# oven.net
KiCad netlist of a schematic drawn in EAGLE
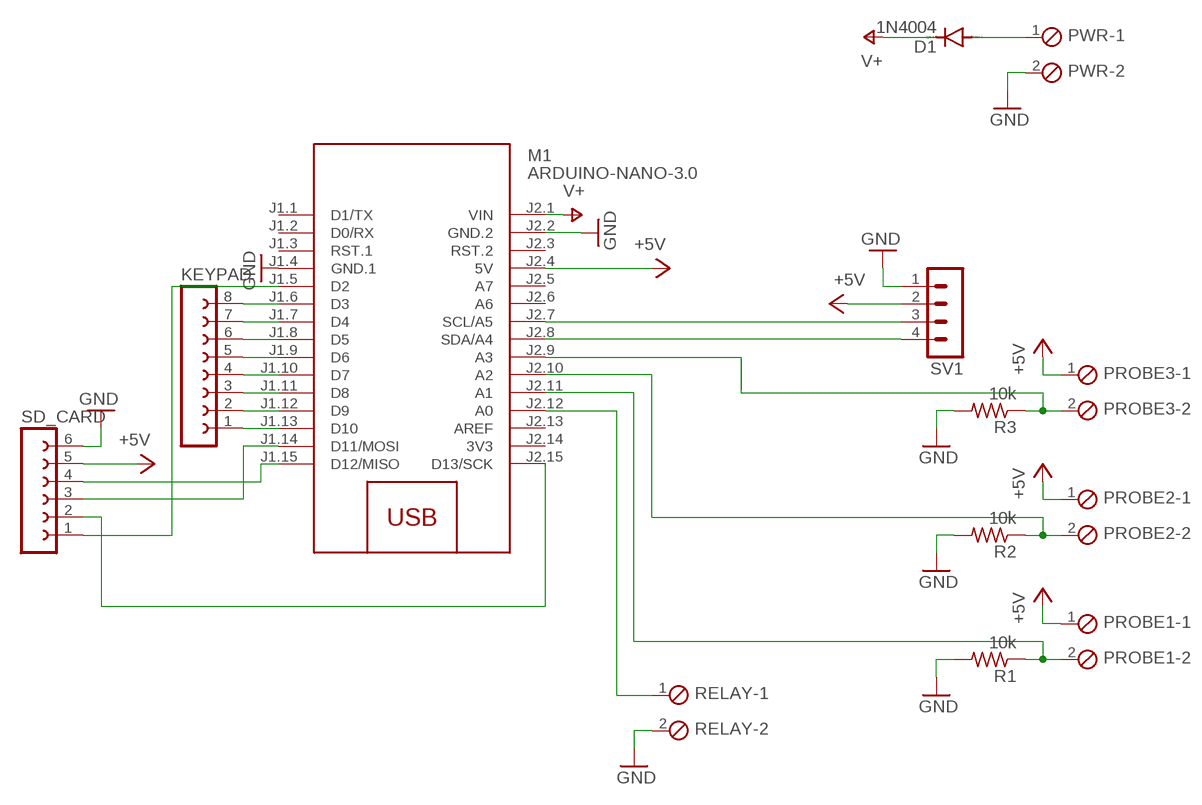
[diagram p0: schematic, sheet 1]

(export (version "E")
  (design (tool "Eeschema 10.0.6"))
  (components
    (comp (ref "D1")
      (value "1N4004")
      (footprint "eagle-import:DO41-10")
      (libsource (lib "eagle-import") (part "1N4004"))
    )
    (comp (ref "KEYPAD")
      (value "FE08-1")
      (footprint "eagle-import:FE08")
      (libsource (lib "eagle-import") (part "FE08-1"))
    )
    (comp (ref "M1")
      (value "ARDUINO-NANO-3.0")
      (footprint "eagle-import:ARDUINO-NANO-3.0")
      (libsource (lib "eagle-import") (part "ARDUINO-NANO-3.0"))
    )
    (comp (ref "PROBE1")
      (value "MPT2")
      (footprint "eagle-import:2POL254")
      (libsource (lib "eagle-import") (part "MPT2"))
    )
    (comp (ref "PROBE2")
      (value "MPT2")
      (footprint "eagle-import:2POL254")
      (libsource (lib "eagle-import") (part "MPT2"))
    )
    (comp (ref "PROBE3")
      (value "MPT2")
      (footprint "eagle-import:2POL254")
      (libsource (lib "eagle-import") (part "MPT2"))
    )
    (comp (ref "PWR")
      (value "MPT2")
      (footprint "eagle-import:2POL254")
      (libsource (lib "eagle-import") (part "MPT2"))
    )
    (comp (ref "R1")
      (value "10k")
      (footprint "eagle-import:0204_5")
      (libsource (lib "eagle-import") (part "R-US_0204/5"))
    )
    (comp (ref "R2")
      (value "10k")
      (footprint "eagle-import:0204_5")
      (libsource (lib "eagle-import") (part "R-US_0204/5"))
    )
    (comp (ref "R3")
      (value "10k")
      (footprint "eagle-import:0204_5")
      (libsource (lib "eagle-import") (part "R-US_0204/5"))
    )
    (comp (ref "RELAY")
      (value "MPT2")
      (footprint "eagle-import:2POL254")
      (libsource (lib "eagle-import") (part "MPT2"))
    )
    (comp (ref "SD_CARD")
      (value "FE06W")
      (footprint "eagle-import:FE06W")
      (libsource (lib "eagle-import") (part "FE06W"))
    )
    (comp (ref "SV1")
      (value "MA04-1")
      (footprint "eagle-import:MA04-1")
      (libsource (lib "eagle-import") (part "MA04-1"))
    )
  )
  (nets
    (net (code "1") (name "+5V") (class "Default")
      (node (ref "M1") (pin "J2.4") (pinfunction "5V_J2.4") (pintype "power_in"))
      (node (ref "PROBE1") (pin "1") (pinfunction "1_1") (pintype "passive"))
      (node (ref "PROBE2") (pin "1") (pinfunction "1_1") (pintype "passive"))
      (node (ref "PROBE3") (pin "1") (pinfunction "1_1") (pintype "passive"))
      (node (ref "SD_CARD") (pin "5") (pinfunction "5_5") (pintype "passive"))
      (node (ref "SV1") (pin "2") (pinfunction "2_2") (pintype "passive"))
    )
    (net (code "2") (name "/3V3") (class "Default")
      (node (ref "M1") (pin "J2.14") (pinfunction "3V3_J2.14") (pintype "power_in"))
    )
    (net (code "3") (name "GND") (class "Default")
      (node (ref "M1") (pin "J1.4") (pinfunction "GND.1_J1.4") (pintype "power_in"))
      (node (ref "M1") (pin "J2.2") (pinfunction "GND.2_J2.2") (pintype "power_in"))
      (node (ref "PWR") (pin "2") (pinfunction "1_2") (pintype "passive"))
      (node (ref "R1") (pin "2") (pinfunction "2_2") (pintype "passive"))
      (node (ref "R2") (pin "2") (pinfunction "2_2") (pintype "passive"))
      (node (ref "R3") (pin "2") (pinfunction "2_2") (pintype "passive"))
      (node (ref "RELAY") (pin "2") (pinfunction "1_2") (pintype "passive"))
      (node (ref "SD_CARD") (pin "6") (pinfunction "6_6") (pintype "passive"))
      (node (ref "SV1") (pin "1") (pinfunction "1_1") (pintype "passive"))
    )
    (net (code "4") (name "Net-(D1-PadA)") (class "Default")
      (node (ref "D1") (pin "A") (pinfunction "A_A") (pintype "passive"))
      (node (ref "PWR") (pin "1") (pinfunction "1_1") (pintype "passive"))
    )
    (net (code "5") (name "Net-(M1-A0)") (class "Default")
      (node (ref "M1") (pin "J2.12") (pinfunction "A0_J2.12") (pintype "bidirectional"))
      (node (ref "RELAY") (pin "1") (pinfunction "1_1") (pintype "passive"))
    )
    (net (code "6") (name "Net-(M1-A1)") (class "Default")
      (node (ref "M1") (pin "J2.11") (pinfunction "A1_J2.11") (pintype "bidirectional"))
      (node (ref "PROBE1") (pin "2") (pinfunction "1_2") (pintype "passive"))
      (node (ref "R1") (pin "1") (pinfunction "1_1") (pintype "passive"))
    )
    (net (code "7") (name "Net-(M1-A2)") (class "Default")
      (node (ref "M1") (pin "J2.10") (pinfunction "A2_J2.10") (pintype "bidirectional"))
      (node (ref "PROBE2") (pin "2") (pinfunction "1_2") (pintype "passive"))
      (node (ref "R2") (pin "1") (pinfunction "1_1") (pintype "passive"))
    )
    (net (code "8") (name "Net-(M1-A3)") (class "Default")
      (node (ref "M1") (pin "J2.9") (pinfunction "A3_J2.9") (pintype "bidirectional"))
      (node (ref "PROBE3") (pin "2") (pinfunction "1_2") (pintype "passive"))
      (node (ref "R3") (pin "1") (pinfunction "1_1") (pintype "passive"))
    )
    (net (code "9") (name "Net-(M1-D2)") (class "Default")
      (node (ref "M1") (pin "J1.5") (pinfunction "D2_J1.5") (pintype "bidirectional"))
      (node (ref "SD_CARD") (pin "1") (pinfunction "1_1") (pintype "passive"))
    )
    (net (code "10") (name "Net-(M1-D3)") (class "Default")
      (node (ref "KEYPAD") (pin "8") (pinfunction "8_8") (pintype "passive"))
      (node (ref "M1") (pin "J1.6") (pinfunction "D3_J1.6") (pintype "bidirectional"))
    )
    (net (code "11") (name "Net-(M1-D4)") (class "Default")
      (node (ref "KEYPAD") (pin "7") (pinfunction "7_7") (pintype "passive"))
      (node (ref "M1") (pin "J1.7") (pinfunction "D4_J1.7") (pintype "bidirectional"))
    )
    (net (code "12") (name "Net-(M1-D5)") (class "Default")
      (node (ref "KEYPAD") (pin "6") (pinfunction "6_6") (pintype "passive"))
      (node (ref "M1") (pin "J1.8") (pinfunction "D5_J1.8") (pintype "bidirectional"))
    )
    (net (code "13") (name "Net-(M1-D6)") (class "Default")
      (node (ref "KEYPAD") (pin "5") (pinfunction "5_5") (pintype "passive"))
      (node (ref "M1") (pin "J1.9") (pinfunction "D6_J1.9") (pintype "bidirectional"))
    )
    (net (code "14") (name "Net-(M1-D7)") (class "Default")
      (node (ref "KEYPAD") (pin "4") (pinfunction "4_4") (pintype "passive"))
      (node (ref "M1") (pin "J1.10") (pinfunction "D7_J1.10") (pintype "bidirectional"))
    )
    (net (code "15") (name "Net-(M1-D8)") (class "Default")
      (node (ref "KEYPAD") (pin "3") (pinfunction "3_3") (pintype "passive"))
      (node (ref "M1") (pin "J1.11") (pinfunction "D8_J1.11") (pintype "bidirectional"))
    )
    (net (code "16") (name "Net-(M1-D9)") (class "Default")
      (node (ref "KEYPAD") (pin "2") (pinfunction "2_2") (pintype "passive"))
      (node (ref "M1") (pin "J1.12") (pinfunction "D9_J1.12") (pintype "bidirectional"))
    )
    (net (code "17") (name "Net-(M1-D10)") (class "Default")
      (node (ref "KEYPAD") (pin "1") (pinfunction "1_1") (pintype "passive"))
      (node (ref "M1") (pin "J1.13") (pinfunction "D10_J1.13") (pintype "bidirectional"))
    )
    (net (code "18") (name "Net-(M1-D11{slash}MOSI)") (class "Default")
      (node (ref "M1") (pin "J1.14") (pinfunction "D11/MOSI_J1.14") (pintype "bidirectional"))
      (node (ref "SD_CARD") (pin "3") (pinfunction "3_3") (pintype "passive"))
    )
    (net (code "19") (name "Net-(M1-D12{slash}MISO)") (class "Default")
      (node (ref "M1") (pin "J1.15") (pinfunction "D12/MISO_J1.15") (pintype "bidirectional"))
      (node (ref "SD_CARD") (pin "4") (pinfunction "4_4") (pintype "passive"))
    )
    (net (code "20") (name "Net-(M1-D13{slash}SCK)") (class "Default")
      (node (ref "M1") (pin "J2.15") (pinfunction "D13/SCK_J2.15") (pintype "bidirectional"))
      (node (ref "SD_CARD") (pin "2") (pinfunction "2_2") (pintype "passive"))
    )
    (net (code "21") (name "Net-(M1-SCL{slash}A5)") (class "Default")
      (node (ref "M1") (pin "J2.7") (pinfunction "SCL/A5_J2.7") (pintype "bidirectional"))
      (node (ref "SV1") (pin "3") (pinfunction "3_3") (pintype "passive"))
    )
    (net (code "22") (name "Net-(M1-SDA{slash}A4)") (class "Default")
      (node (ref "M1") (pin "J2.8") (pinfunction "SDA/A4_J2.8") (pintype "bidirectional"))
      (node (ref "SV1") (pin "4") (pinfunction "4_4") (pintype "passive"))
    )
    (net (code "23") (name "V+") (class "Default")
      (node (ref "D1") (pin "C") (pinfunction "C_C") (pintype "passive"))
      (node (ref "M1") (pin "J2.1") (pinfunction "VIN_J2.1") (pintype "power_in"))
    )
    (net (code "24") (name "unconnected-(M1-A6-PadJ2.6)") (class "Default")
      (node (ref "M1") (pin "J2.6") (pinfunction "A6_J2.6") (pintype "bidirectional"))
    )
    (net (code "25") (name "unconnected-(M1-A7-PadJ2.5)") (class "Default")
      (node (ref "M1") (pin "J2.5") (pinfunction "A7_J2.5") (pintype "bidirectional"))
    )
    (net (code "26") (name "unconnected-(M1-AREF-PadJ2.13)") (class "Default")
      (node (ref "M1") (pin "J2.13") (pinfunction "AREF_J2.13") (pintype "bidirectional"))
    )
    (net (code "27") (name "unconnected-(M1-D0{slash}RX-PadJ1.2)") (class "Default")
      (node (ref "M1") (pin "J1.2") (pinfunction "D0/RX_J1.2") (pintype "bidirectional"))
    )
    (net (code "28") (name "unconnected-(M1-D1{slash}TX-PadJ1.1)") (class "Default")
      (node (ref "M1") (pin "J1.1") (pinfunction "D1/TX_J1.1") (pintype "bidirectional"))
    )
    (net (code "29") (name "unconnected-(M1-RST.1-PadJ1.3)") (class "Default")
      (node (ref "M1") (pin "J1.3") (pinfunction "RST.1_J1.3") (pintype "bidirectional"))
    )
    (net (code "30") (name "unconnected-(M1-RST.2-PadJ2.3)") (class "Default")
      (node (ref "M1") (pin "J2.3") (pinfunction "RST.2_J2.3") (pintype "bidirectional"))
    )
  )
)
